# 24V_to_3V3_regulator.net
KiCad netlist of a schematic drawn in Altium Designer
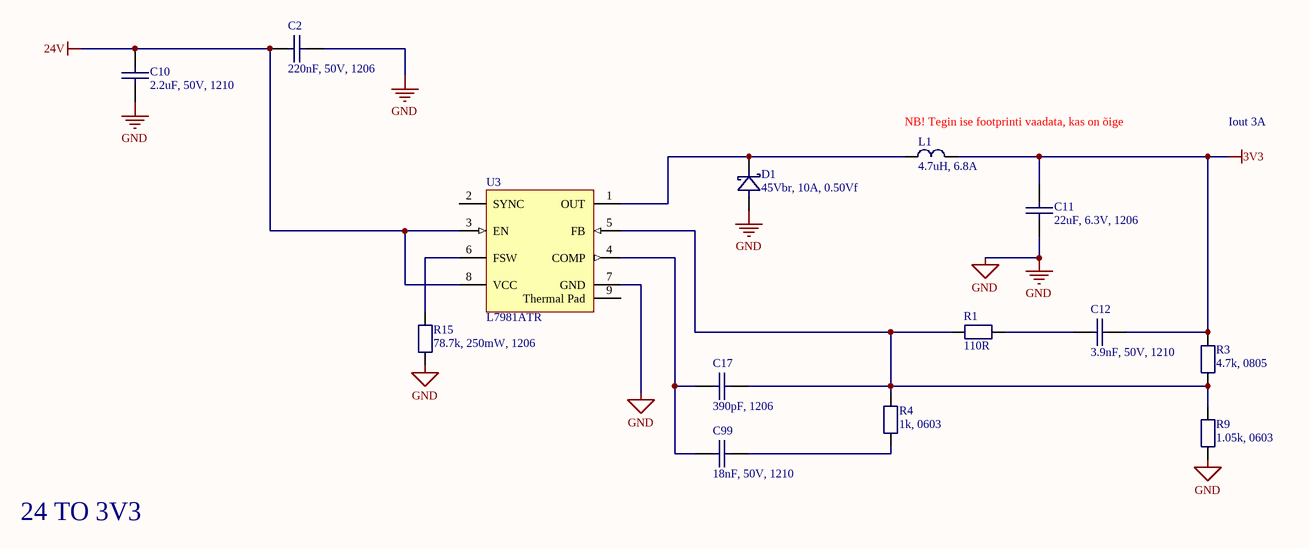
[diagram p0: 24V_to_3V3_regulator.SchDoc]

(export (version "E")
  (design (tool "Eeschema 10.0.6"))
  (components
    (comp (ref "C2")
      (value "220nF, 50V, 1206")
      (footprint "3216 [1206] CAP")
      (libsource (lib "AS_component_library") (part "Capacitor"))
    )
    (comp (ref "C10")
      (value "2.2uF, 50V, 1210")
      (footprint "3225 [1210] CAP")
      (libsource (lib "AS_component_library") (part "Capacitor"))
    )
    (comp (ref "C11")
      (value "22uF, 6.3V, 1206")
      (footprint "3216 [1206] CAP")
      (libsource (lib "AS_component_library") (part "Capacitor"))
    )
    (comp (ref "C12")
      (value "3.9nF, 50V, 1210")
      (footprint "3225 [1210] CAP")
      (libsource (lib "AS_component_library") (part "Capacitor"))
    )
    (comp (ref "C17")
      (value "390pF, 1206")
      (footprint "3216 [1206] CAP")
      (libsource (lib "AS_component_library") (part "Capacitor"))
    )
    (comp (ref "C99")
      (value "18nF, 50V, 1210")
      (footprint "2012 [0805] CAP")
      (libsource (lib "AS_component_library") (part "Capacitor"))
    )
    (comp (ref "D1")
      (value "45Vbr, 10A, 0.50Vf")
      (footprint "DPAK (TO252-3)")
      (libsource (lib "AS_component_library") (part "Diode Shottky"))
    )
    (comp (ref "L1")
      (value "4.7uH, 6.8A")
      (footprint "12.5 x 12.5 x 8.5 (mm)")
      (libsource (lib "AS_component_library") (part "Inductor"))
    )
    (comp (ref "R1")
      (value "110R")
      (footprint "2012 [0805] RES")
      (libsource (lib "AS_component_library") (part "Resistor"))
    )
    (comp (ref "R3")
      (value "4.7k, 0805")
      (footprint "2012 [0805] RES")
      (libsource (lib "AS_component_library") (part "Resistor"))
    )
    (comp (ref "R4")
      (value "1k, 0603")
      (footprint "1608 [0603] RES")
      (libsource (lib "AS_component_library") (part "Resistor"))
    )
    (comp (ref "R9")
      (value "1.05k, 0603")
      (footprint "1608 [0603] RES")
      (libsource (lib "AS_component_library") (part "Resistor"))
    )
    (comp (ref "R15")
      (value "78.7k, 250mW, 1206")
      (footprint "3216 [1206] RES")
      (libsource (lib "AS_component_library") (part "Resistor"))
    )
    (comp (ref "U3")
      (value "L7981ATR")
      (footprint "HSOP8-D1_N")
      (description "3 A step-down switching regulator, 8-Pin HSOP, Tape and Reel")
      (libsource (lib "STMicroelectronics Power Management DC-DC Conversion") (part "L7981ATR"))
    )
  )
  (nets
    (net (code "1") (name "3V3") (class "Default")
      (node (ref "C11") (pin "1") (pinfunction "1_1") (pintype "passive"))
      (node (ref "C12") (pin "1") (pinfunction "1_1") (pintype "passive"))
      (node (ref "L1") (pin "2") (pinfunction "2_2") (pintype "passive"))
      (node (ref "R3") (pin "2") (pinfunction "2_2") (pintype "passive"))
    )
    (net (code "2") (name "24V") (class "Default")
      (node (ref "C10") (pin "1") (pinfunction "1_1") (pintype "passive"))
      (node (ref "C2") (pin "2") (pinfunction "2_2") (pintype "passive"))
      (node (ref "U3") (pin "3") (pinfunction "EN_3") (pintype "input"))
      (node (ref "U3") (pin "8") (pinfunction "VCC_8") (pintype "power_in"))
    )
    (net (code "3") (name "GND") (class "Default")
      (node (ref "C10") (pin "2") (pinfunction "2_2") (pintype "passive"))
      (node (ref "C11") (pin "2") (pinfunction "2_2") (pintype "passive"))
      (node (ref "C2") (pin "1") (pinfunction "1_1") (pintype "passive"))
      (node (ref "D1") (pin "2") (pinfunction "2_2") (pintype "passive"))
      (node (ref "R15") (pin "1") (pinfunction "1_1") (pintype "passive"))
      (node (ref "R9") (pin "1") (pinfunction "1_1") (pintype "passive"))
      (node (ref "U3") (pin "7") (pinfunction "GND_7") (pintype "power_in"))
    )
    (net (code "4") (name "Net-(C12-Pad2)") (class "Default")
      (node (ref "C12") (pin "2") (pinfunction "2_2") (pintype "passive"))
      (node (ref "R1") (pin "2") (pinfunction "2_2") (pintype "passive"))
    )
    (net (code "5") (name "Net-(C99-Pad1)") (class "Default")
      (node (ref "C99") (pin "1") (pinfunction "1_1") (pintype "passive"))
      (node (ref "R4") (pin "1") (pinfunction "1_1") (pintype "passive"))
    )
    (net (code "6") (name "Net-(U3-COMP)") (class "Default")
      (node (ref "C17") (pin "2") (pinfunction "2_2") (pintype "passive"))
      (node (ref "C99") (pin "2") (pinfunction "2_2") (pintype "passive"))
      (node (ref "U3") (pin "4") (pinfunction "COMP_4") (pintype "output"))
    )
    (net (code "7") (name "Net-(U3-FB)") (class "Default")
      (node (ref "C17") (pin "1") (pinfunction "1_1") (pintype "passive"))
      (node (ref "R1") (pin "1") (pinfunction "1_1") (pintype "passive"))
      (node (ref "R3") (pin "1") (pinfunction "1_1") (pintype "passive"))
      (node (ref "R4") (pin "2") (pinfunction "2_2") (pintype "passive"))
      (node (ref "R9") (pin "2") (pinfunction "2_2") (pintype "passive"))
      (node (ref "U3") (pin "5") (pinfunction "FB_5") (pintype "input"))
    )
    (net (code "8") (name "Net-(U3-FSW)") (class "Default")
      (node (ref "R15") (pin "2") (pinfunction "2_2") (pintype "passive"))
      (node (ref "U3") (pin "6") (pinfunction "FSW_6") (pintype "passive"))
    )
    (net (code "9") (name "Net-(U3-OUT)") (class "Default")
      (node (ref "D1") (pin "1") (pinfunction "1_1") (pintype "passive"))
      (node (ref "L1") (pin "1") (pinfunction "1_1") (pintype "passive"))
      (node (ref "U3") (pin "1") (pinfunction "OUT_1") (pintype "power_in"))
    )
    (net (code "10") (name "unconnected-(U3-SYNC-Pad2)") (class "Default")
      (node (ref "U3") (pin "2") (pinfunction "SYNC_2") (pintype "passive"))
    )
    (net (code "11") (name "unconnected-(U3-Thermal_Pad-Pad9)") (class "Default")
      (node (ref "U3") (pin "9") (pinfunction "Thermal_Pad_9") (pintype "power_in"))
    )
  )
)
